# ZPZH.net
KiCad netlist of a schematic drawn in Altium Designer
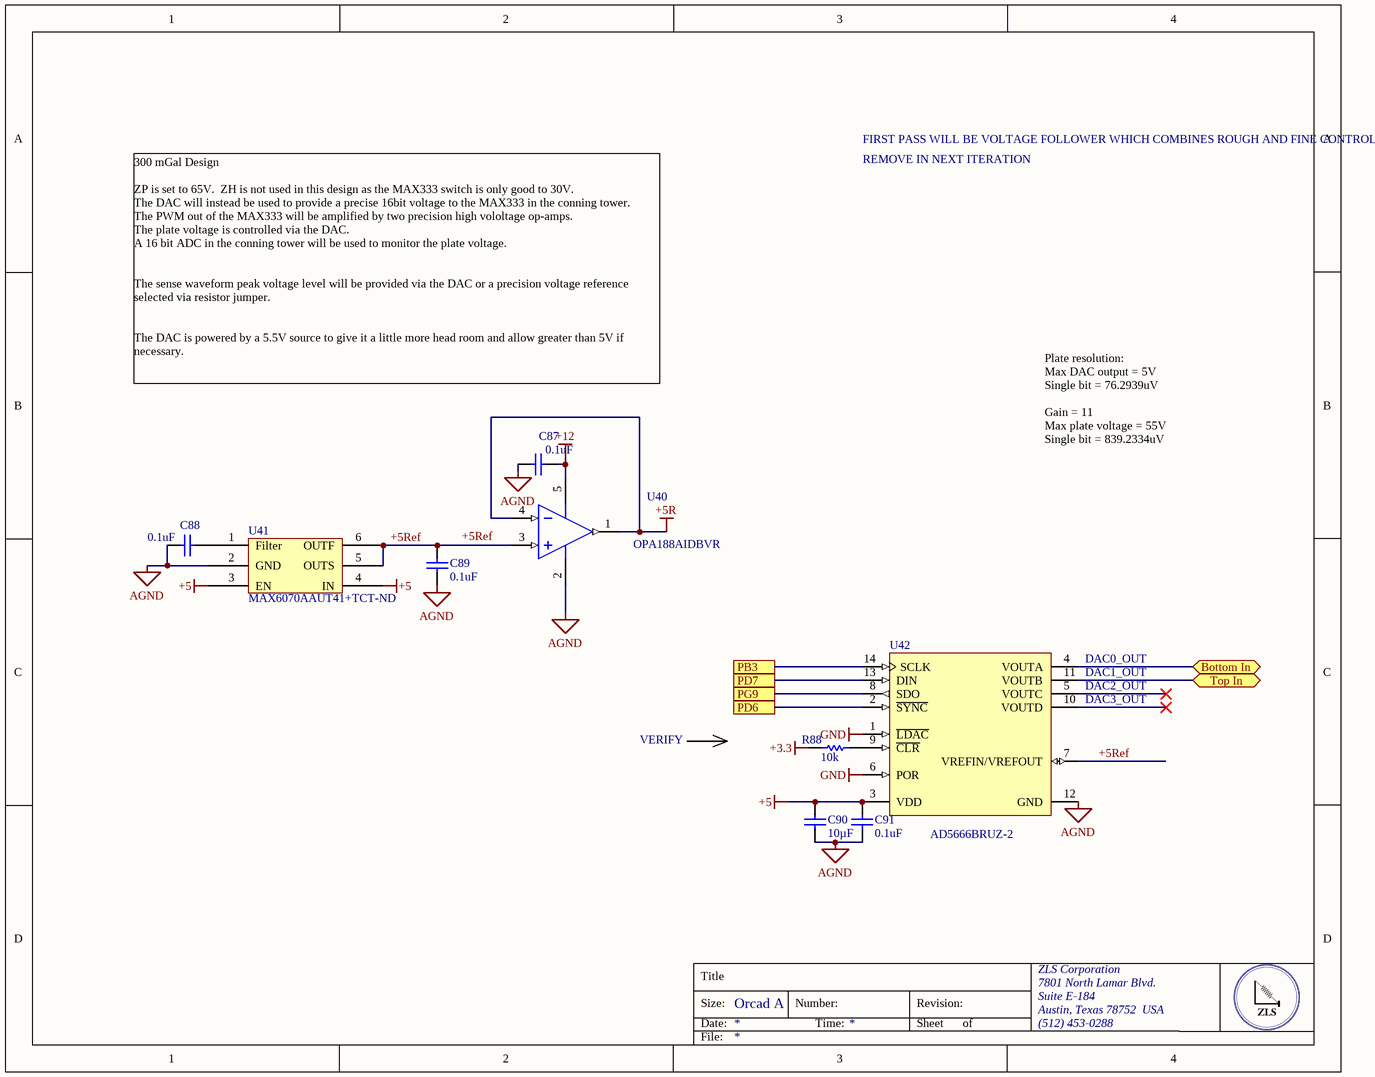
[diagram p0: ZPZH.SchDoc]

(export (version "E")
  (design (tool "Eeschema 10.0.6"))
  (components
    (comp (ref "C87")
      (value "0.1uF")
      (footprint "CAPC0402(1005)60_L")
      (description "CAP CER 0.1UF 10V X7R 0402")
      (fields
        (field (name "MANUFACTURER") "Murata Electronics North America")
        (field (name "MANUFACTURER PART NUMBER") "GRM155R71A104KA01D")
      )
      (libsource (lib "Altium Content Vault") (part "CMP-1034-00252-1"))
    )
    (comp (ref "C88")
      (value "0.1uF")
      (footprint "CAPC0402(1005)60_L")
      (description "CAP CER 0.1UF 10V X7R 0402")
      (fields
        (field (name "MANUFACTURER") "Murata Electronics North America")
        (field (name "MANUFACTURER PART NUMBER") "GRM155R71A104KA01D")
      )
      (libsource (lib "Altium Content Vault") (part "CMP-1034-00252-1"))
    )
    (comp (ref "C89")
      (value "0.1uF")
      (footprint "CAPC0402(1005)60_L")
      (description "CAP CER 0.1UF 10V X7R 0402")
      (fields
        (field (name "MANUFACTURER") "Murata Electronics North America")
        (field (name "MANUFACTURER PART NUMBER") "GRM155R71A104KA01D")
      )
      (libsource (lib "Altium Content Vault") (part "CMP-1034-00252-1"))
    )
    (comp (ref "C90")
      (value "10uF")
      (footprint "CAPC0805(2012)145_N")
      (description "CAP CER 10UF 25V X7R 0805")
      (fields
        (field (name "MANUFACTURER") "Murata Electronics North America")
        (field (name "MANUFACTURER PART NUMBER") "GRM21BR71E104KA01L")
        (field (name "CAPACITANCE") "10µF")
      )
      (libsource (lib "Altium Content Vault") (part "CMP-1036-04795-1"))
    )
    (comp (ref "C91")
      (value "0.1uF")
      (footprint "CAPC0402(1005)60_L")
      (description "CAP CER 0.1UF 10V X7R 0402")
      (fields
        (field (name "MANUFACTURER") "Murata Electronics North America")
        (field (name "MANUFACTURER PART NUMBER") "GRM155R71A104KA01D")
      )
      (libsource (lib "Altium Content Vault") (part "CMP-1034-00252-1"))
    )
    (comp (ref "R88")
      (value "10k")
      (footprint "RESC0402(1005)_M")
      (description "10k 0.063W 1% 0402 (1005 Metric)  SMD")
      (fields
        (field (name "MANUFACTURER") "Panasonic")
        (field (name "MANUFACTURER PART NUMBER") "ERJ-2RKF1002X")
      )
      (libsource (lib "Altium Content Vault") (part "RES"))
    )
    (comp (ref "U40")
      (value "OPA188AIDBVR")
      (footprint "DBV0005A_M")
      (fields (field (name "MANUFACTURER") "Texas Instruments"))
      (libsource (lib "Altium Content Vault") (part "CMP-0809-00005-2"))
    )
    (comp (ref "U41")
      (value "MAX6070AAUT41+T")
      (footprint "SOT95P280X445-6N")
      (description "IC VREF SERIES 4.096V SOT23")
      (fields
        (field (name "SUPPLIER PART NUMBER 1") "MAX6070AAUT41+TCT-ND")
        (field (name "MANUFACTURER") "Maxim Integrated")
        (field (name "TOLERANCE") "±0.04%")
      )
      (libsource (lib "ZLS_Schematic_lib") (part "MAX6070AAUT41+T"))
    )
    (comp (ref "U42")
      (value "AD5666BRUZ-2")
      (footprint "RU-14_N")
      (fields (field (name "GENERIC PART NUMBER") "AD5666") (field (name "MANUFACTURER") "Analog Devices"))
      (libsource (lib "Altium Content Vault") (part "CMP-0318-01541-2"))
    )
  )
  (nets
    (net (code "1") (name "+3.3") (class "Default")
      (node (ref "R88") (pin "1") (pinfunction "1_1") (pintype "passive"))
    )
    (net (code "2") (name "+5") (class "Default")
      (node (ref "C90") (pin "2") (pinfunction "2_2") (pintype "passive"))
      (node (ref "C91") (pin "1") (pinfunction "1_1") (pintype "passive"))
      (node (ref "U41") (pin "3") (pinfunction "EN_3") (pintype "passive"))
      (node (ref "U41") (pin "4") (pinfunction "IN_4") (pintype "passive"))
      (node (ref "U42") (pin "3") (pinfunction "VDD_3") (pintype "power_in"))
    )
    (net (code "3") (name "+5R") (class "Default")
      (node (ref "U40") (pin "1") (pinfunction "OUT_1") (pintype "output"))
      (node (ref "U40") (pin "4") (pinfunction "IN-_4") (pintype "input"))
    )
    (net (code "4") (name "+12") (class "Default")
      (node (ref "C87") (pin "1") (pinfunction "1_1") (pintype "passive"))
      (node (ref "U40") (pin "5") (pinfunction "V+_5") (pintype "power_in"))
    )
    (net (code "5") (name "/+5Ref") (class "Default")
      (node (ref "C89") (pin "2") (pinfunction "2_2") (pintype "passive"))
      (node (ref "U40") (pin "3") (pinfunction "IN+_3") (pintype "input"))
      (node (ref "U41") (pin "5") (pinfunction "OUTS_5") (pintype "passive"))
      (node (ref "U41") (pin "6") (pinfunction "OUTF_6") (pintype "passive"))
      (node (ref "U42") (pin "7") (pinfunction "VREFIN/VREFOUT_7") (pintype "bidirectional"))
    )
    (net (code "6") (name "/Bottom In") (class "Default")
      (node (ref "U42") (pin "4") (pinfunction "VOUTA_4") (pintype "tri_state"))
    )
    (net (code "7") (name "/PB3") (class "Default")
      (node (ref "U42") (pin "14") (pinfunction "SCLK_14") (pintype "input"))
    )
    (net (code "8") (name "/PD6") (class "Default")
      (node (ref "U42") (pin "2") (pinfunction "~{SYNC}_2") (pintype "input"))
    )
    (net (code "9") (name "/PD7") (class "Default")
      (node (ref "U42") (pin "13") (pinfunction "DIN_13") (pintype "input"))
    )
    (net (code "10") (name "/PG9") (class "Default")
      (node (ref "U42") (pin "8") (pinfunction "SDO_8") (pintype "output"))
    )
    (net (code "11") (name "/Top In") (class "Default")
      (node (ref "U42") (pin "11") (pinfunction "VOUTB_11") (pintype "tri_state"))
    )
    (net (code "12") (name "AGND") (class "Default")
      (node (ref "C87") (pin "2") (pinfunction "2_2") (pintype "passive"))
      (node (ref "C88") (pin "2") (pinfunction "2_2") (pintype "passive"))
      (node (ref "C89") (pin "1") (pinfunction "1_1") (pintype "passive"))
      (node (ref "C90") (pin "1") (pinfunction "1_1") (pintype "passive"))
      (node (ref "C91") (pin "2") (pinfunction "2_2") (pintype "passive"))
      (node (ref "U40") (pin "2") (pinfunction "V-_2") (pintype "power_in"))
      (node (ref "U41") (pin "2") (pinfunction "GND_2") (pintype "passive"))
      (node (ref "U42") (pin "12") (pinfunction "GND_12") (pintype "power_in"))
    )
    (net (code "13") (name "GND") (class "Default")
      (node (ref "U42") (pin "1") (pinfunction "~{LDAC}_1") (pintype "input"))
      (node (ref "U42") (pin "6") (pinfunction "POR_6") (pintype "input"))
    )
    (net (code "14") (name "Net-(U41-Filter)") (class "Default")
      (node (ref "C88") (pin "1") (pinfunction "1_1") (pintype "passive"))
      (node (ref "U41") (pin "1") (pinfunction "Filter_1") (pintype "passive"))
    )
    (net (code "15") (name "Net-(U42-~{CLR})") (class "Default")
      (node (ref "R88") (pin "2") (pinfunction "2_2") (pintype "passive"))
      (node (ref "U42") (pin "9") (pinfunction "~{CLR}_9") (pintype "input"))
    )
    (net (code "16") (name "unconnected-(U42-VOUTC-Pad5)") (class "Default")
      (node (ref "U42") (pin "5") (pinfunction "VOUTC_5") (pintype "tri_state+no_connect"))
    )
    (net (code "17") (name "unconnected-(U42-VOUTD-Pad10)") (class "Default")
      (node (ref "U42") (pin "10") (pinfunction "VOUTD_10") (pintype "tri_state+no_connect"))
    )
  )
)
